# PMB.net
KiCad netlist of a schematic drawn in EAGLE
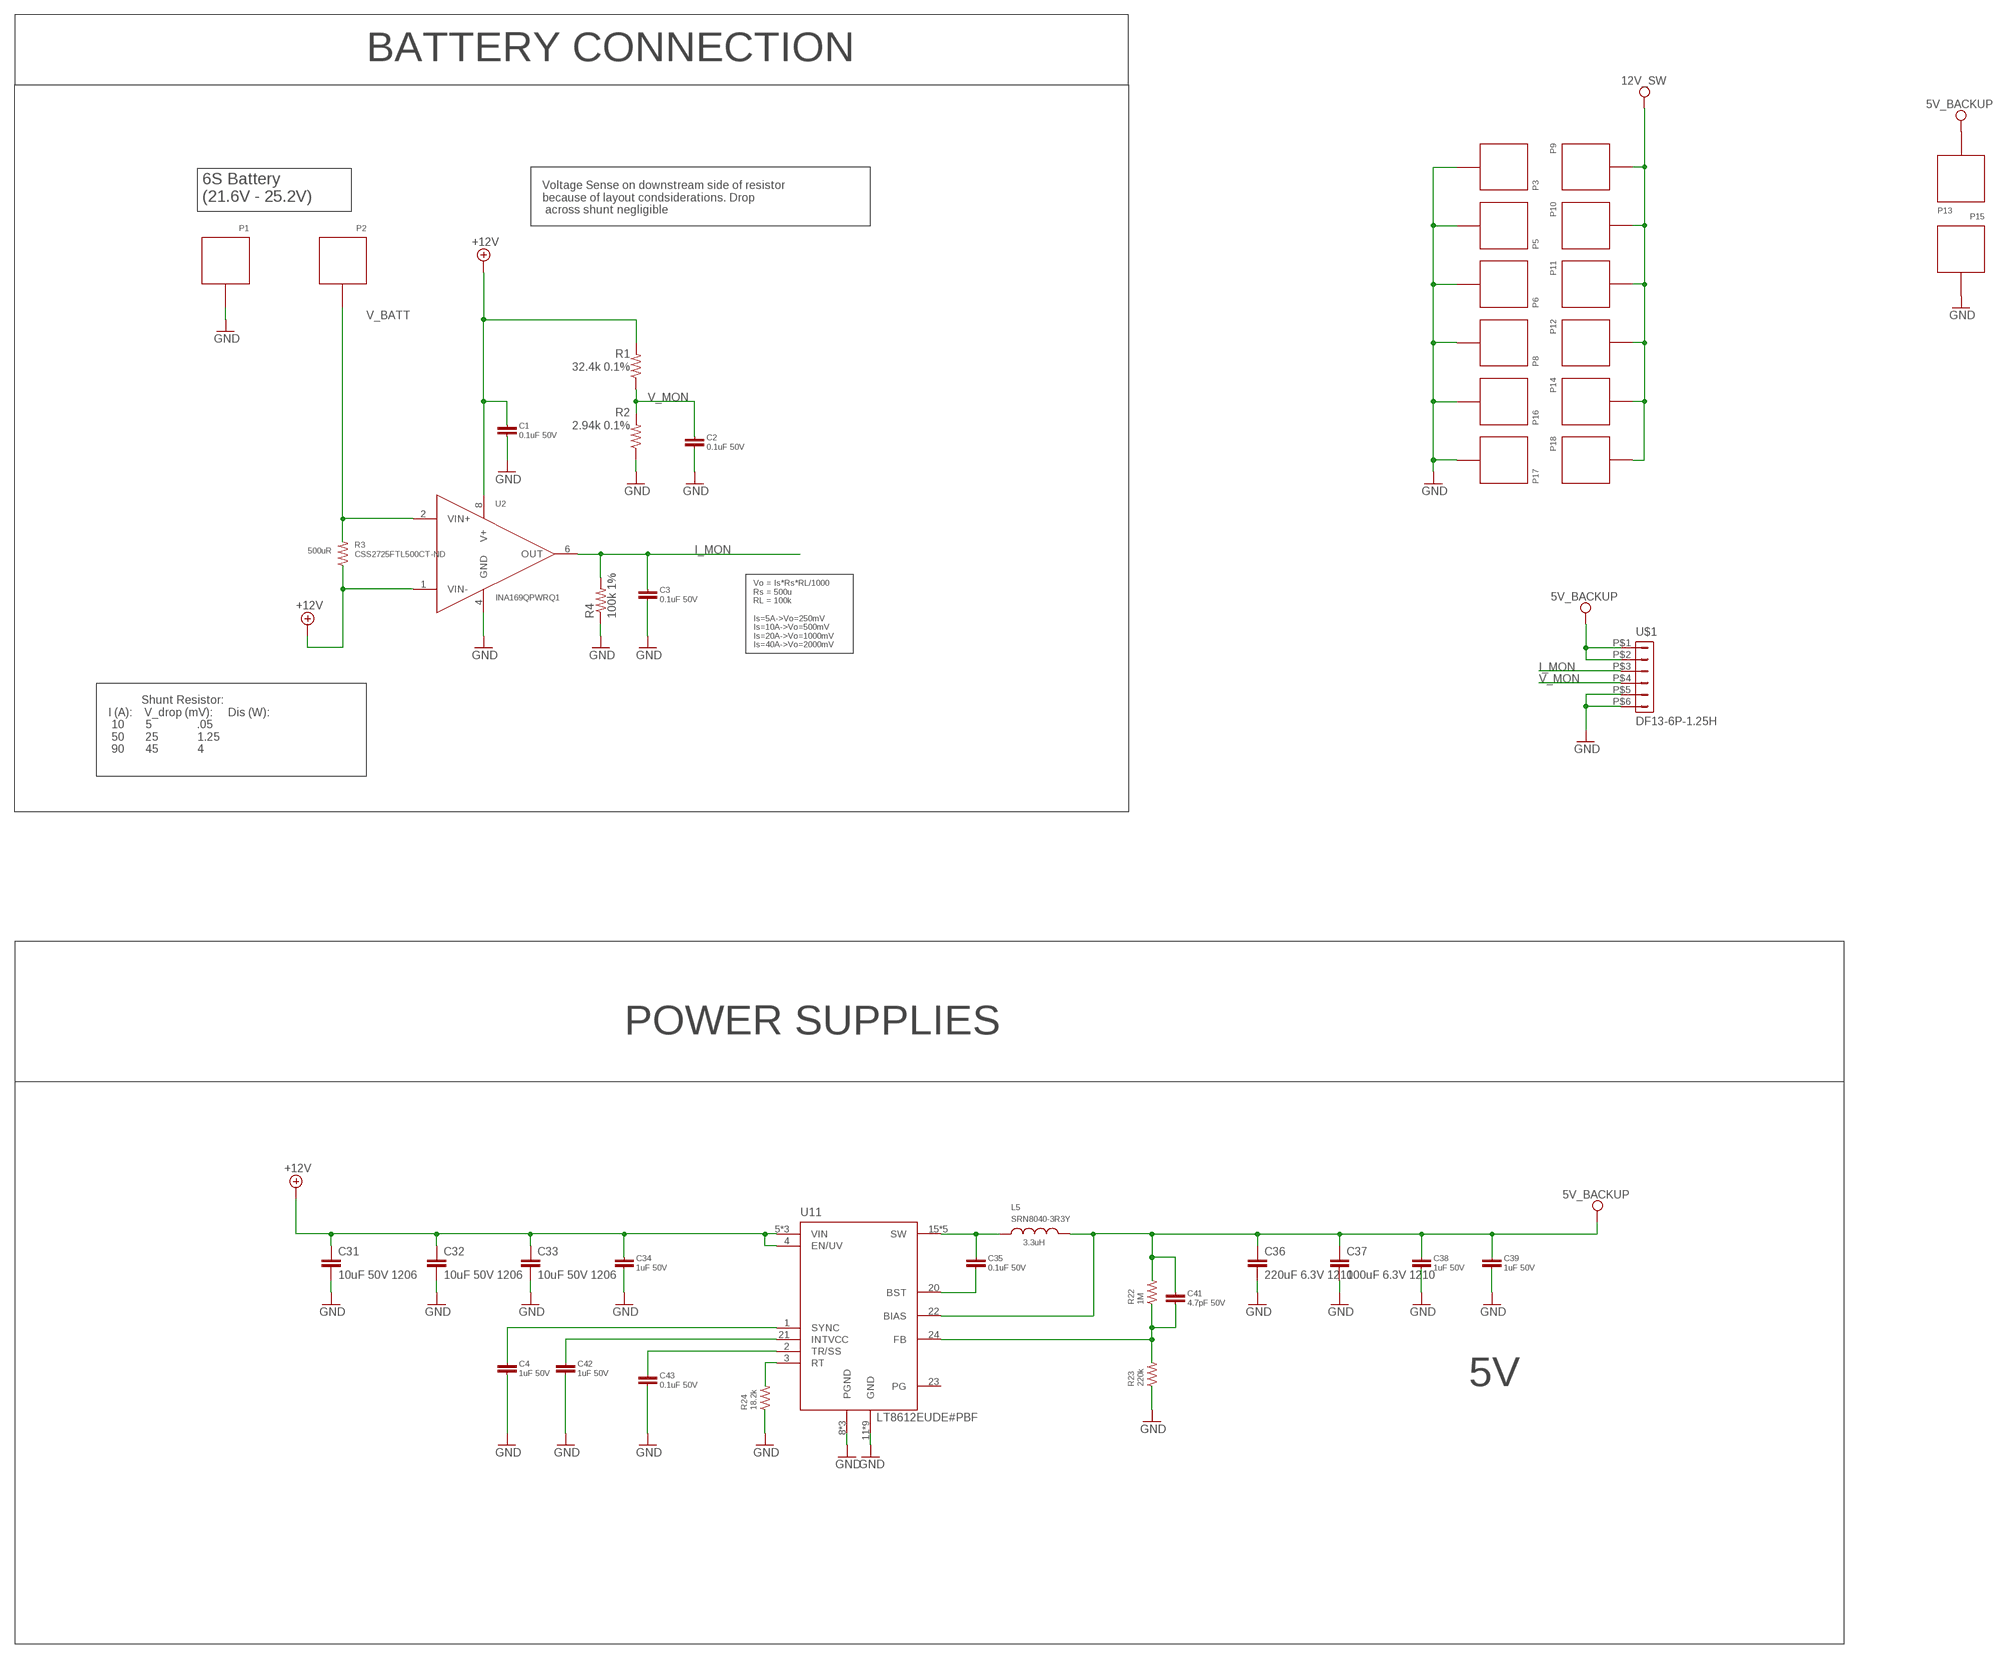
[diagram p0: schematic, sheet 1, part 1 of 2]
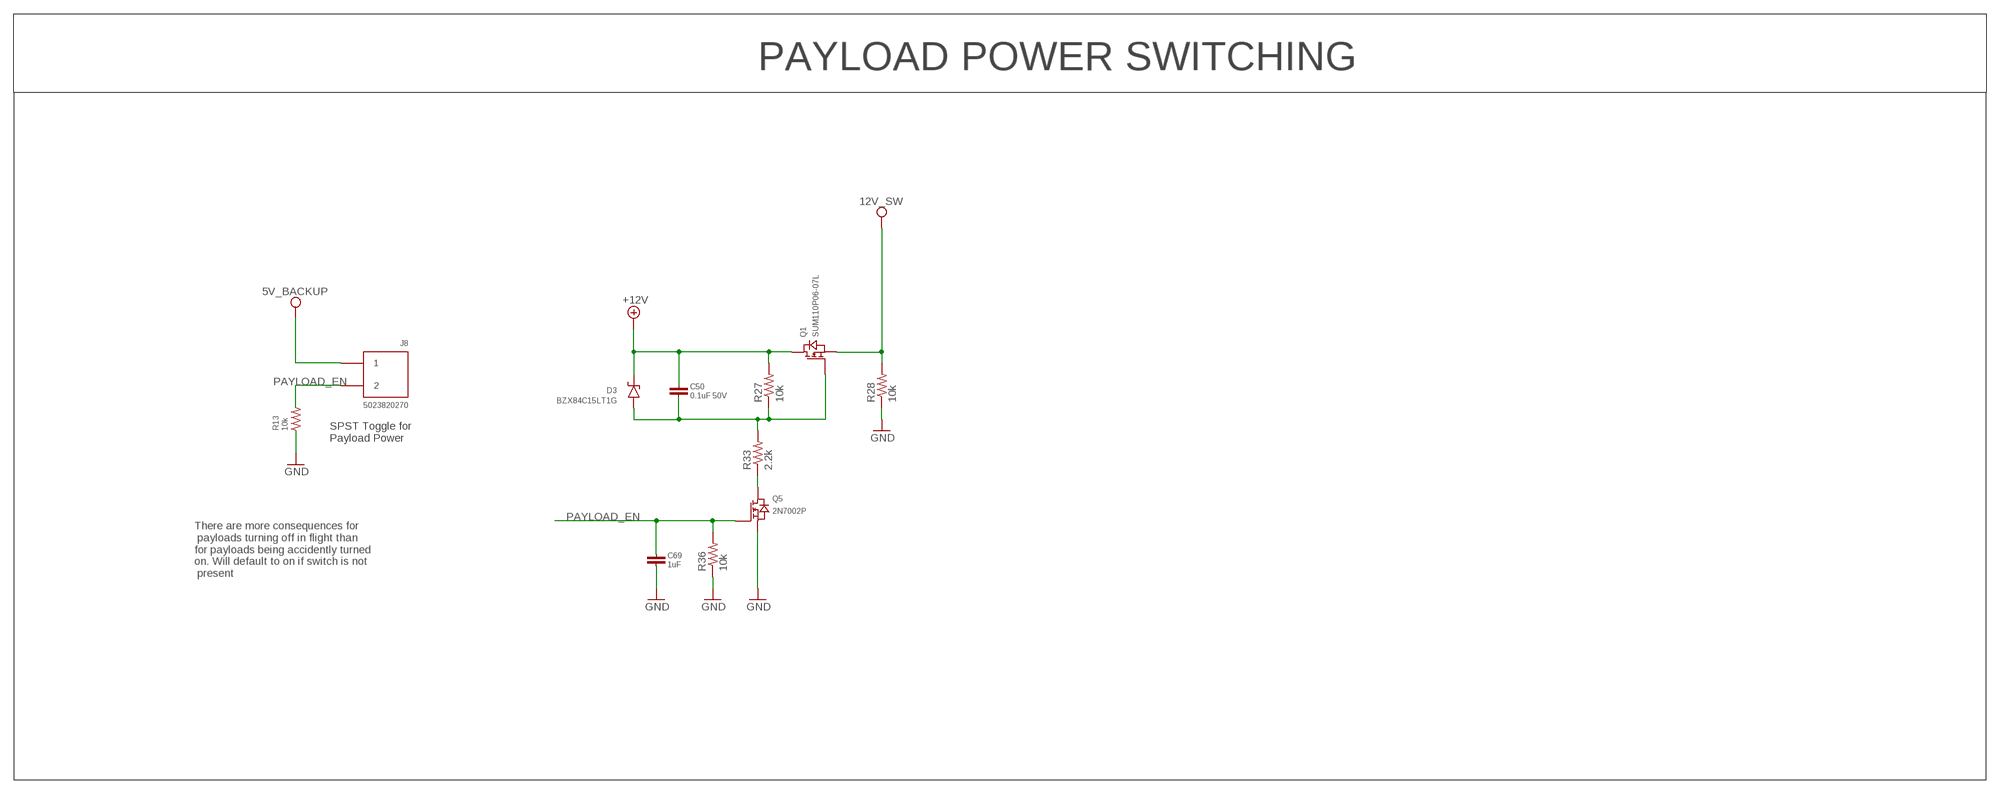
[diagram p1: schematic, sheet 1, part 2 of 2]

(export (version "E")
  (design (tool "Eeschema 10.0.6"))
  (components
    (comp (ref "C1")
      (value "0.1uF 50V")
      (footprint "eagle-import:0805")
      (libsource (lib "eagle-import") (part "CAP_(4)"))
    )
    (comp (ref "C2")
      (value "0.1uF 50V")
      (footprint "eagle-import:0805")
      (libsource (lib "eagle-import") (part "CAP_(4)"))
    )
    (comp (ref "C3")
      (value "0.1uF 50V")
      (footprint "eagle-import:0805")
      (libsource (lib "eagle-import") (part "CAP_(4)"))
    )
    (comp (ref "C4")
      (value "1uF 50V")
      (footprint "eagle-import:0805")
      (libsource (lib "eagle-import") (part "CAP_(4)"))
    )
    (comp (ref "C31")
      (value "10uF 50V 1206")
      (footprint "eagle-import:1206")
      (libsource (lib "eagle-import") (part "CAP1206"))
    )
    (comp (ref "C32")
      (value "10uF 50V 1206")
      (footprint "eagle-import:1206")
      (libsource (lib "eagle-import") (part "CAP1206"))
    )
    (comp (ref "C33")
      (value "10uF 50V 1206")
      (footprint "eagle-import:1206")
      (libsource (lib "eagle-import") (part "CAP1206"))
    )
    (comp (ref "C34")
      (value "1uF 50V")
      (footprint "eagle-import:0805")
      (libsource (lib "eagle-import") (part "CAP_(4)"))
    )
    (comp (ref "C35")
      (value "0.1uF 50V")
      (footprint "eagle-import:0805")
      (libsource (lib "eagle-import") (part "CAP_(4)"))
    )
    (comp (ref "C36")
      (value "220uF 6.3V 1210")
      (footprint "eagle-import:1210")
      (libsource (lib "eagle-import") (part "CAP1210"))
    )
    (comp (ref "C37")
      (value "100uF 6.3V 1210")
      (footprint "eagle-import:1210")
      (libsource (lib "eagle-import") (part "CAP1210"))
    )
    (comp (ref "C38")
      (value "1uF 50V")
      (footprint "eagle-import:0805")
      (libsource (lib "eagle-import") (part "CAP_(4)"))
    )
    (comp (ref "C39")
      (value "1uF 50V")
      (footprint "eagle-import:0805")
      (libsource (lib "eagle-import") (part "CAP_(4)"))
    )
    (comp (ref "C41")
      (value "4.7pF 50V")
      (footprint "eagle-import:0805")
      (libsource (lib "eagle-import") (part "CAP_(4)"))
    )
    (comp (ref "C42")
      (value "1uF 50V")
      (footprint "eagle-import:0805")
      (libsource (lib "eagle-import") (part "CAP_(4)"))
    )
    (comp (ref "C43")
      (value "0.1uF 50V")
      (footprint "eagle-import:0805")
      (libsource (lib "eagle-import") (part "CAP_(4)"))
    )
    (comp (ref "C50")
      (value "0.1uF 50V")
      (footprint "eagle-import:0805")
      (libsource (lib "eagle-import") (part "CAP_(4)"))
    )
    (comp (ref "C69")
      (value "1uF")
      (footprint "eagle-import:0805")
      (libsource (lib "eagle-import") (part "CAP_(4)"))
    )
    (comp (ref "D3")
      (value "BZX84C15LT1G")
      (footprint "eagle-import:SOT-23-3")
      (libsource (lib "eagle-import") (part "ZENER_1A_3C"))
    )
    (comp (ref "J8")
      (value "5023820270")
      (footprint "eagle-import:CLIK-MATE_1.25MM_2")
      (libsource (lib "eagle-import") (part "CON_2PIN_(1)"))
    )
    (comp (ref "L5")
      (value "SRN8040-3R3Y")
      (footprint "eagle-import:BOURNS_SRN8040")
      (libsource (lib "eagle-import") (part "INDUCTOR_(B3)"))
    )
    (comp (ref "P1")
      (value "SOLDER_PAD_(1)")
      (footprint "eagle-import:SOLDER_PAD_10X5")
      (libsource (lib "eagle-import") (part "SOLDER_PAD_(1)"))
    )
    (comp (ref "P2")
      (value "SOLDER_PAD_(1)")
      (footprint "eagle-import:SOLDER_PAD_10X5")
      (libsource (lib "eagle-import") (part "SOLDER_PAD_(1)"))
    )
    (comp (ref "P3")
      (value "SOLDER_PAD_(10)")
      (footprint "eagle-import:SOLDER_PAD_3X6")
      (libsource (lib "eagle-import") (part "SOLDER_PAD_(10)"))
    )
    (comp (ref "P5")
      (value "SOLDER_PAD_(10)")
      (footprint "eagle-import:SOLDER_PAD_3X6")
      (libsource (lib "eagle-import") (part "SOLDER_PAD_(10)"))
    )
    (comp (ref "P6")
      (value "SOLDER_PAD_(10)")
      (footprint "eagle-import:SOLDER_PAD_3X6")
      (libsource (lib "eagle-import") (part "SOLDER_PAD_(10)"))
    )
    (comp (ref "P8")
      (value "SOLDER_PAD_(10)")
      (footprint "eagle-import:SOLDER_PAD_3X6")
      (libsource (lib "eagle-import") (part "SOLDER_PAD_(10)"))
    )
    (comp (ref "P9")
      (value "SOLDER_PAD_(10)")
      (footprint "eagle-import:SOLDER_PAD_3X6")
      (libsource (lib "eagle-import") (part "SOLDER_PAD_(10)"))
    )
    (comp (ref "P10")
      (value "SOLDER_PAD_(10)")
      (footprint "eagle-import:SOLDER_PAD_3X6")
      (libsource (lib "eagle-import") (part "SOLDER_PAD_(10)"))
    )
    (comp (ref "P11")
      (value "SOLDER_PAD_(10)")
      (footprint "eagle-import:SOLDER_PAD_3X6")
      (libsource (lib "eagle-import") (part "SOLDER_PAD_(10)"))
    )
    (comp (ref "P12")
      (value "SOLDER_PAD_(10)")
      (footprint "eagle-import:SOLDER_PAD_3X6")
      (libsource (lib "eagle-import") (part "SOLDER_PAD_(10)"))
    )
    (comp (ref "P13")
      (value "SOLDER_PAD_(15)")
      (footprint "eagle-import:SOLDER_PAD_2X4")
      (libsource (lib "eagle-import") (part "SOLDER_PAD_(15)"))
    )
    (comp (ref "P14")
      (value "SOLDER_PAD_(10)")
      (footprint "eagle-import:SOLDER_PAD_3X6")
      (libsource (lib "eagle-import") (part "SOLDER_PAD_(10)"))
    )
    (comp (ref "P15")
      (value "SOLDER_PAD_(15)")
      (footprint "eagle-import:SOLDER_PAD_2X4")
      (libsource (lib "eagle-import") (part "SOLDER_PAD_(15)"))
    )
    (comp (ref "P16")
      (value "SOLDER_PAD_(10)")
      (footprint "eagle-import:SOLDER_PAD_3X6")
      (libsource (lib "eagle-import") (part "SOLDER_PAD_(10)"))
    )
    (comp (ref "P17")
      (value "SOLDER_PAD_(10)")
      (footprint "eagle-import:SOLDER_PAD_3X6")
      (libsource (lib "eagle-import") (part "SOLDER_PAD_(10)"))
    )
    (comp (ref "P18")
      (value "SOLDER_PAD_(10)")
      (footprint "eagle-import:SOLDER_PAD_3X6")
      (libsource (lib "eagle-import") (part "SOLDER_PAD_(10)"))
    )
    (comp (ref "Q1")
      (value "SUM110P06-07L")
      (footprint "eagle-import:TO-263-3_INFINEON")
      (libsource (lib "eagle-import") (part "NMOS_GDS"))
    )
    (comp (ref "Q5")
      (value "2N7002P")
      (footprint "eagle-import:SOT-23-3")
      (libsource (lib "eagle-import") (part "NMOS_GSD(1)"))
    )
    (comp (ref "R1")
      (value "32.4k 0.1%")
      (footprint "eagle-import:R0805")
      (libsource (lib "eagle-import") (part "R-US_R0805"))
    )
    (comp (ref "R2")
      (value "2.94k 0.1%")
      (footprint "eagle-import:R0805")
      (libsource (lib "eagle-import") (part "R-US_R0805"))
    )
    (comp (ref "R3")
      (value "CSS2725FTL500CT-ND")
      (footprint "eagle-import:2725")
      (libsource (lib "eagle-import") (part "RESISTOR_(4)"))
    )
    (comp (ref "R4")
      (value "100k 1%")
      (footprint "eagle-import:R0805")
      (libsource (lib "eagle-import") (part "R-US_R0805"))
    )
    (comp (ref "R13")
      (value "10k")
      (footprint "eagle-import:0805")
      (libsource (lib "eagle-import") (part "RESISTOR_(7)"))
    )
    (comp (ref "R22")
      (value "1M")
      (footprint "eagle-import:0805")
      (libsource (lib "eagle-import") (part "RESISTOR_(7)"))
    )
    (comp (ref "R23")
      (value "220k")
      (footprint "eagle-import:0805")
      (libsource (lib "eagle-import") (part "RESISTOR_(7)"))
    )
    (comp (ref "R24")
      (value "18.2k")
      (footprint "eagle-import:0805")
      (libsource (lib "eagle-import") (part "RESISTOR_(7)"))
    )
    (comp (ref "R27")
      (value "10k")
      (footprint "eagle-import:R0805")
      (libsource (lib "eagle-import") (part "R-US_R0805"))
    )
    (comp (ref "R28")
      (value "10k")
      (footprint "eagle-import:R0805")
      (libsource (lib "eagle-import") (part "R-US_R0805"))
    )
    (comp (ref "R33")
      (value "2.2k")
      (footprint "eagle-import:R0805")
      (libsource (lib "eagle-import") (part "R-US_R0805"))
    )
    (comp (ref "R36")
      (value "10k")
      (footprint "eagle-import:R0805")
      (libsource (lib "eagle-import") (part "R-US_R0805"))
    )
    (comp (ref "U$1")
      (value "DF13-6P-1.25H")
      (footprint "eagle-import:DF13A-6P-1.25H")
      (libsource (lib "eagle-import") (part "DF13-6P-1.25H"))
    )
    (comp (ref "U2")
      (value "INA169QPWRQ1")
      (footprint "eagle-import:TSSOP-8")
      (libsource (lib "eagle-import") (part "INA169"))
    )
    (comp (ref "U11")
      (value "LT8612EUDE#PBF")
      (footprint "eagle-import:WFQFN-28")
      (libsource (lib "eagle-import") (part "LT8612"))
    )
  )
  (nets
    (net (code "1") (name "+12V") (class "Default")
      (node (ref "C1") (pin "1") (pinfunction "1_1") (pintype "passive"))
      (node (ref "C31") (pin "1") (pinfunction "1_1") (pintype "passive"))
      (node (ref "C32") (pin "1") (pinfunction "1_1") (pintype "passive"))
      (node (ref "C33") (pin "1") (pinfunction "1_1") (pintype "passive"))
      (node (ref "C34") (pin "1") (pinfunction "1_1") (pintype "passive"))
      (node (ref "C50") (pin "1") (pinfunction "1_1") (pintype "passive"))
      (node (ref "D3") (pin "3") (pinfunction "C_3") (pintype "passive"))
      (node (ref "Q1") (pin "2") (pinfunction "D_2") (pintype "bidirectional"))
      (node (ref "R1") (pin "2") (pinfunction "2_2") (pintype "passive"))
      (node (ref "R27") (pin "2") (pinfunction "2_2") (pintype "passive"))
      (node (ref "R3") (pin "1") (pinfunction "1_1") (pintype "passive"))
      (node (ref "U11") (pin "4") (pinfunction "EN/UV_4") (pintype "bidirectional"))
      (node (ref "U11") (pin "5") (pinfunction "VIN_5") (pintype "bidirectional"))
      (node (ref "U11") (pin "6") (pinfunction "VIN_6") (pintype "bidirectional"))
      (node (ref "U11") (pin "7") (pinfunction "VIN_7") (pintype "bidirectional"))
      (node (ref "U2") (pin "1") (pinfunction "VIN-_1") (pintype "bidirectional"))
      (node (ref "U2") (pin "8") (pinfunction "V+_8") (pintype "bidirectional"))
    )
    (net (code "2") (name "/I_MON") (class "Default")
      (node (ref "C3") (pin "1") (pinfunction "1_1") (pintype "passive"))
      (node (ref "R4") (pin "2") (pinfunction "2_2") (pintype "passive"))
      (node (ref "U$1") (pin "P$3") (pinfunction "3_P$3") (pintype "passive"))
      (node (ref "U2") (pin "6") (pinfunction "OUT_6") (pintype "bidirectional"))
    )
    (net (code "3") (name "/PAYLOAD_EN") (class "Default")
      (node (ref "C69") (pin "1") (pinfunction "1_1") (pintype "passive"))
      (node (ref "J8") (pin "2") (pinfunction "2_2") (pintype "bidirectional"))
      (node (ref "Q5") (pin "1") (pinfunction "G_1") (pintype "bidirectional"))
      (node (ref "R13") (pin "2") (pinfunction "2_2") (pintype "passive"))
      (node (ref "R36") (pin "2") (pinfunction "2_2") (pintype "passive"))
    )
    (net (code "4") (name "/V_BATT") (class "Default")
      (node (ref "P2") (pin "1") (pinfunction "P$1_1") (pintype "bidirectional"))
      (node (ref "R3") (pin "2") (pinfunction "2_2") (pintype "passive"))
      (node (ref "U2") (pin "2") (pinfunction "VIN+_2") (pintype "bidirectional"))
    )
    (net (code "5") (name "/V_MON") (class "Default")
      (node (ref "C2") (pin "1") (pinfunction "1_1") (pintype "passive"))
      (node (ref "R1") (pin "1") (pinfunction "1_1") (pintype "passive"))
      (node (ref "R2") (pin "2") (pinfunction "2_2") (pintype "passive"))
      (node (ref "U$1") (pin "P$4") (pinfunction "4_P$4") (pintype "passive"))
    )
    (net (code "6") (name "5V_BACKUP") (class "Default")
      (node (ref "C36") (pin "1") (pinfunction "1_1") (pintype "passive"))
      (node (ref "C37") (pin "1") (pinfunction "1_1") (pintype "passive"))
      (node (ref "C38") (pin "1") (pinfunction "1_1") (pintype "passive"))
      (node (ref "C39") (pin "1") (pinfunction "1_1") (pintype "passive"))
      (node (ref "C41") (pin "1") (pinfunction "1_1") (pintype "passive"))
      (node (ref "J8") (pin "1") (pinfunction "1_1") (pintype "bidirectional"))
      (node (ref "L5") (pin "2") (pinfunction "2_2") (pintype "passive"))
      (node (ref "P13") (pin "P$1") (pinfunction "P$1_P$1") (pintype "bidirectional"))
      (node (ref "R22") (pin "2") (pinfunction "2_2") (pintype "passive"))
      (node (ref "U$1") (pin "P$1") (pinfunction "1_P$1") (pintype "passive"))
      (node (ref "U$1") (pin "P$2") (pinfunction "2_P$2") (pintype "passive"))
      (node (ref "U11") (pin "22") (pinfunction "BIAS_22") (pintype "bidirectional"))
    )
    (net (code "7") (name "12V_SW") (class "Default")
      (node (ref "P10") (pin "P$1") (pinfunction "P$1_P$1") (pintype "bidirectional"))
      (node (ref "P11") (pin "P$1") (pinfunction "P$1_P$1") (pintype "bidirectional"))
      (node (ref "P12") (pin "P$1") (pinfunction "P$1_P$1") (pintype "bidirectional"))
      (node (ref "P14") (pin "P$1") (pinfunction "P$1_P$1") (pintype "bidirectional"))
      (node (ref "P18") (pin "P$1") (pinfunction "P$1_P$1") (pintype "bidirectional"))
      (node (ref "P9") (pin "P$1") (pinfunction "P$1_P$1") (pintype "bidirectional"))
      (node (ref "Q1") (pin "3") (pinfunction "S_3") (pintype "bidirectional"))
      (node (ref "R28") (pin "2") (pinfunction "2_2") (pintype "passive"))
    )
    (net (code "8") (name "GND") (class "Default")
      (node (ref "C1") (pin "2") (pinfunction "2_2") (pintype "passive"))
      (node (ref "C2") (pin "2") (pinfunction "2_2") (pintype "passive"))
      (node (ref "C3") (pin "2") (pinfunction "2_2") (pintype "passive"))
      (node (ref "C31") (pin "2") (pinfunction "2_2") (pintype "passive"))
      (node (ref "C32") (pin "2") (pinfunction "2_2") (pintype "passive"))
      (node (ref "C33") (pin "2") (pinfunction "2_2") (pintype "passive"))
      (node (ref "C34") (pin "2") (pinfunction "2_2") (pintype "passive"))
      (node (ref "C36") (pin "2") (pinfunction "2_2") (pintype "passive"))
      (node (ref "C37") (pin "2") (pinfunction "2_2") (pintype "passive"))
      (node (ref "C38") (pin "2") (pinfunction "2_2") (pintype "passive"))
      (node (ref "C39") (pin "2") (pinfunction "2_2") (pintype "passive"))
      (node (ref "C4") (pin "2") (pinfunction "2_2") (pintype "passive"))
      (node (ref "C42") (pin "2") (pinfunction "2_2") (pintype "passive"))
      (node (ref "C43") (pin "2") (pinfunction "2_2") (pintype "passive"))
      (node (ref "C69") (pin "2") (pinfunction "2_2") (pintype "passive"))
      (node (ref "P1") (pin "1") (pinfunction "P$1_1") (pintype "bidirectional"))
      (node (ref "P15") (pin "P$1") (pinfunction "P$1_P$1") (pintype "bidirectional"))
      (node (ref "P16") (pin "P$1") (pinfunction "P$1_P$1") (pintype "bidirectional"))
      (node (ref "P17") (pin "P$1") (pinfunction "P$1_P$1") (pintype "bidirectional"))
      (node (ref "P3") (pin "P$1") (pinfunction "P$1_P$1") (pintype "bidirectional"))
      (node (ref "P5") (pin "P$1") (pinfunction "P$1_P$1") (pintype "bidirectional"))
      (node (ref "P6") (pin "P$1") (pinfunction "P$1_P$1") (pintype "bidirectional"))
      (node (ref "P8") (pin "P$1") (pinfunction "P$1_P$1") (pintype "bidirectional"))
      (node (ref "Q5") (pin "2") (pinfunction "S_2") (pintype "bidirectional"))
      (node (ref "R13") (pin "1") (pinfunction "1_1") (pintype "passive"))
      (node (ref "R2") (pin "1") (pinfunction "1_1") (pintype "passive"))
      (node (ref "R23") (pin "1") (pinfunction "1_1") (pintype "passive"))
      (node (ref "R24") (pin "1") (pinfunction "1_1") (pintype "passive"))
      (node (ref "R28") (pin "1") (pinfunction "1_1") (pintype "passive"))
      (node (ref "R36") (pin "1") (pinfunction "1_1") (pintype "passive"))
      (node (ref "R4") (pin "1") (pinfunction "1_1") (pintype "passive"))
      (node (ref "U$1") (pin "P$5") (pinfunction "5_P$5") (pintype "passive"))
      (node (ref "U$1") (pin "P$6") (pinfunction "6_P$6") (pintype "passive"))
      (node (ref "U11") (pin "10") (pinfunction "PGND_10") (pintype "bidirectional"))
      (node (ref "U11") (pin "11") (pinfunction "GND_11") (pintype "bidirectional"))
      (node (ref "U11") (pin "12") (pinfunction "GND_12") (pintype "bidirectional"))
      (node (ref "U11") (pin "13") (pinfunction "GND_13") (pintype "bidirectional"))
      (node (ref "U11") (pin "14") (pinfunction "GND_14") (pintype "bidirectional"))
      (node (ref "U11") (pin "25") (pinfunction "GND_25") (pintype "bidirectional"))
      (node (ref "U11") (pin "26") (pinfunction "GND_26") (pintype "bidirectional"))
      (node (ref "U11") (pin "27") (pinfunction "GND_27") (pintype "bidirectional"))
      (node (ref "U11") (pin "28") (pinfunction "GND_28") (pintype "bidirectional"))
      (node (ref "U11") (pin "29") (pinfunction "GND_29") (pintype "bidirectional"))
      (node (ref "U11") (pin "8") (pinfunction "PGND_8") (pintype "bidirectional"))
      (node (ref "U11") (pin "9") (pinfunction "PGND_9") (pintype "bidirectional"))
      (node (ref "U2") (pin "4") (pinfunction "GND_4") (pintype "bidirectional"))
    )
    (net (code "9") (name "Net-(C35-Pad1)") (class "Default")
      (node (ref "C35") (pin "1") (pinfunction "1_1") (pintype "passive"))
      (node (ref "L5") (pin "1") (pinfunction "1_1") (pintype "passive"))
      (node (ref "U11") (pin "15") (pinfunction "SW_15") (pintype "bidirectional"))
      (node (ref "U11") (pin "16") (pinfunction "SW_16") (pintype "bidirectional"))
      (node (ref "U11") (pin "17") (pinfunction "SW_17") (pintype "bidirectional"))
      (node (ref "U11") (pin "18") (pinfunction "SW_18") (pintype "bidirectional"))
      (node (ref "U11") (pin "19") (pinfunction "SW_19") (pintype "bidirectional"))
    )
    (net (code "10") (name "Net-(D3-A)") (class "Default")
      (node (ref "C50") (pin "2") (pinfunction "2_2") (pintype "passive"))
      (node (ref "D3") (pin "1") (pinfunction "A_1") (pintype "passive"))
      (node (ref "Q1") (pin "1") (pinfunction "G_1") (pintype "bidirectional"))
      (node (ref "R27") (pin "1") (pinfunction "1_1") (pintype "passive"))
      (node (ref "R33") (pin "2") (pinfunction "2_2") (pintype "passive"))
    )
    (net (code "11") (name "Net-(Q5-D)") (class "Default")
      (node (ref "Q5") (pin "3") (pinfunction "D_3") (pintype "bidirectional"))
      (node (ref "R33") (pin "1") (pinfunction "1_1") (pintype "passive"))
    )
    (net (code "12") (name "Net-(U11-BST)") (class "Default")
      (node (ref "C35") (pin "2") (pinfunction "2_2") (pintype "passive"))
      (node (ref "U11") (pin "20") (pinfunction "BST_20") (pintype "bidirectional"))
    )
    (net (code "13") (name "Net-(U11-FB)") (class "Default")
      (node (ref "C41") (pin "2") (pinfunction "2_2") (pintype "passive"))
      (node (ref "R22") (pin "1") (pinfunction "1_1") (pintype "passive"))
      (node (ref "R23") (pin "2") (pinfunction "2_2") (pintype "passive"))
      (node (ref "U11") (pin "24") (pinfunction "FB_24") (pintype "bidirectional"))
    )
    (net (code "14") (name "Net-(U11-INTVCC)") (class "Default")
      (node (ref "C42") (pin "1") (pinfunction "1_1") (pintype "passive"))
      (node (ref "U11") (pin "21") (pinfunction "INTVCC_21") (pintype "bidirectional"))
    )
    (net (code "15") (name "Net-(U11-RT)") (class "Default")
      (node (ref "R24") (pin "2") (pinfunction "2_2") (pintype "passive"))
      (node (ref "U11") (pin "3") (pinfunction "RT_3") (pintype "bidirectional"))
    )
    (net (code "16") (name "Net-(U11-SYNC)") (class "Default")
      (node (ref "C4") (pin "1") (pinfunction "1_1") (pintype "passive"))
      (node (ref "U11") (pin "1") (pinfunction "SYNC_1") (pintype "bidirectional"))
    )
    (net (code "17") (name "Net-(U11-TR{slash}SS)") (class "Default")
      (node (ref "C43") (pin "1") (pinfunction "1_1") (pintype "passive"))
      (node (ref "U11") (pin "2") (pinfunction "TR/SS_2") (pintype "bidirectional"))
    )
    (net (code "18") (name "unconnected-(U11-PG-Pad23)") (class "Default")
      (node (ref "U11") (pin "23") (pinfunction "PG_23") (pintype "bidirectional"))
    )
  )
)
